# 5-Band_50W_PA_50W_PA.net
KiCad netlist of a schematic drawn in EAGLE
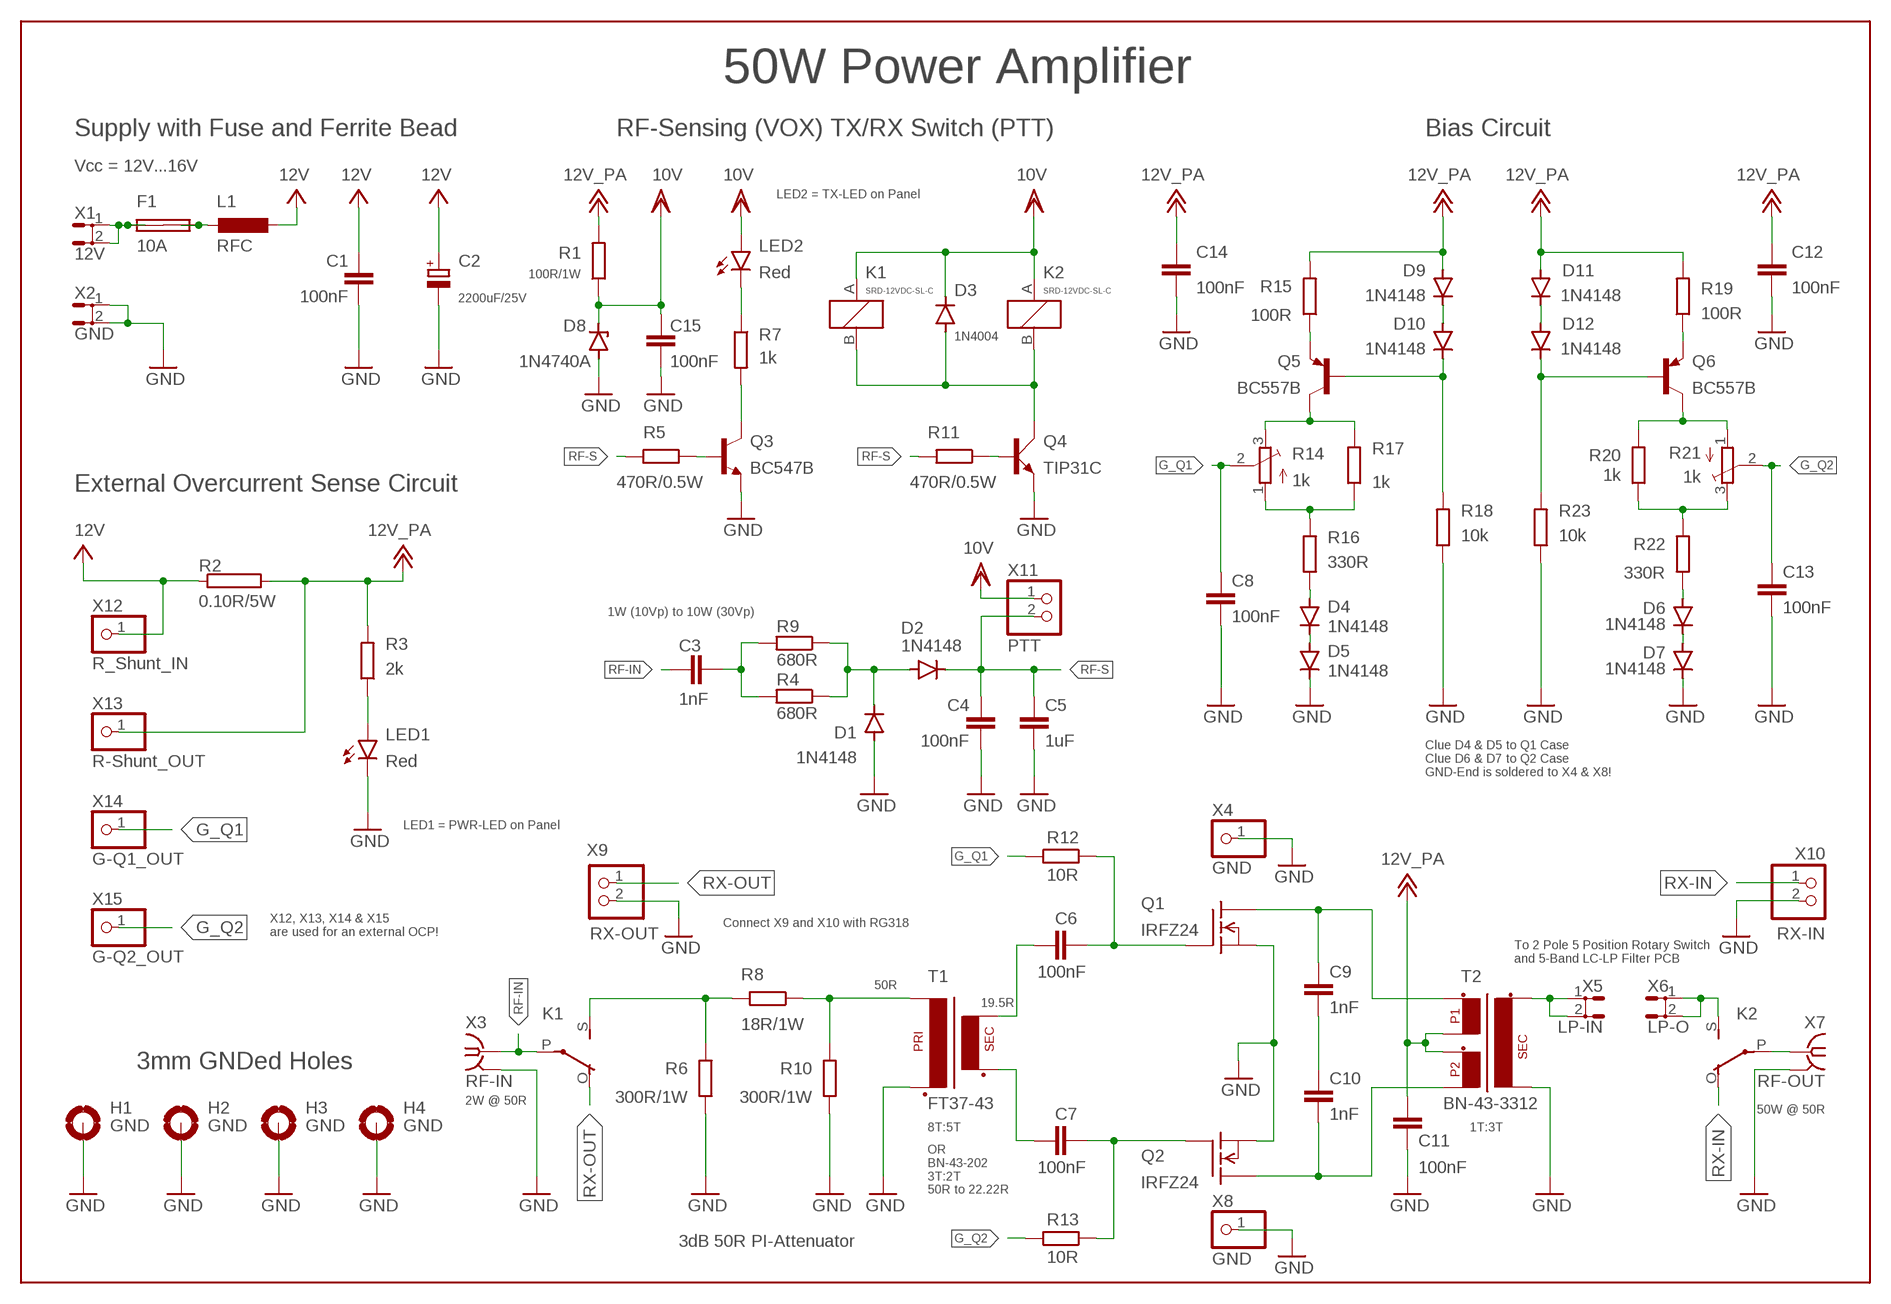
[diagram p0: schematic, sheet 1]

(export (version "E")
  (design (tool "Eeschema 10.0.6"))
  (components
    (comp (ref "C1")
      (value "100nF")
      (footprint "eagle-import:C0805")
      (libsource (lib "eagle-import") (part "C-EUC0805"))
    )
    (comp (ref "C2")
      (value "2200uF/25V")
      (footprint "eagle-import:E7,5-16")
      (libsource (lib "eagle-import") (part "CPOL-EUE7.5-16"))
    )
    (comp (ref "C3")
      (value "1nF")
      (footprint "eagle-import:C0805")
      (libsource (lib "eagle-import") (part "C-EUC0805"))
    )
    (comp (ref "C4")
      (value "100nF")
      (footprint "eagle-import:C0805")
      (libsource (lib "eagle-import") (part "C-EUC0805"))
    )
    (comp (ref "C5")
      (value "1uF")
      (footprint "eagle-import:C0805")
      (libsource (lib "eagle-import") (part "C-EUC0805"))
    )
    (comp (ref "C6")
      (value "100nF")
      (footprint "eagle-import:C0805")
      (libsource (lib "eagle-import") (part "C-EUC0805"))
    )
    (comp (ref "C7")
      (value "100nF")
      (footprint "eagle-import:C0805")
      (libsource (lib "eagle-import") (part "C-EUC0805"))
    )
    (comp (ref "C8")
      (value "100nF")
      (footprint "eagle-import:C0805")
      (libsource (lib "eagle-import") (part "C-EUC0805"))
    )
    (comp (ref "C9")
      (value "1nF")
      (footprint "eagle-import:C1206K")
      (libsource (lib "eagle-import") (part "C-EUC1206K"))
    )
    (comp (ref "C10")
      (value "1nF")
      (footprint "eagle-import:C1206K")
      (libsource (lib "eagle-import") (part "C-EUC1206K"))
    )
    (comp (ref "C11")
      (value "100nF")
      (footprint "eagle-import:C0805")
      (libsource (lib "eagle-import") (part "C-EUC0805"))
    )
    (comp (ref "C12")
      (value "100nF")
      (footprint "eagle-import:C0805")
      (libsource (lib "eagle-import") (part "C-EUC0805"))
    )
    (comp (ref "C13")
      (value "100nF")
      (footprint "eagle-import:C0805")
      (libsource (lib "eagle-import") (part "C-EUC0805"))
    )
    (comp (ref "C14")
      (value "100nF")
      (footprint "eagle-import:C0805")
      (libsource (lib "eagle-import") (part "C-EUC0805"))
    )
    (comp (ref "C15")
      (value "100nF")
      (footprint "eagle-import:C0805")
      (libsource (lib "eagle-import") (part "C-EUC0805"))
    )
    (comp (ref "D1")
      (value "1N4148")
      (footprint "eagle-import:SOD323-W")
      (libsource (lib "eagle-import") (part "DIODE-SOD323-W"))
    )
    (comp (ref "D2")
      (value "1N4148")
      (footprint "eagle-import:SOD323-W")
      (libsource (lib "eagle-import") (part "DIODE-SOD323-W"))
    )
    (comp (ref "D3")
      (value "1N4004")
      (footprint "eagle-import:DO41-10")
      (libsource (lib "eagle-import") (part "1N4004"))
    )
    (comp (ref "D4")
      (value "1N4148")
      (footprint "eagle-import:DO35-7")
      (libsource (lib "eagle-import") (part "1N4148DO35-7"))
    )
    (comp (ref "D5")
      (value "1N4148")
      (footprint "eagle-import:DO35-7")
      (libsource (lib "eagle-import") (part "1N4148DO35-7"))
    )
    (comp (ref "D6")
      (value "1N4148")
      (footprint "eagle-import:DO35-7")
      (libsource (lib "eagle-import") (part "1N4148DO35-7"))
    )
    (comp (ref "D7")
      (value "1N4148")
      (footprint "eagle-import:DO35-7")
      (libsource (lib "eagle-import") (part "1N4148DO35-7"))
    )
    (comp (ref "D8")
      (value "1N4740A")
      (footprint "eagle-import:DO41Z10")
      (libsource (lib "eagle-import") (part "1N4728"))
    )
    (comp (ref "D9")
      (value "1N4148")
      (footprint "eagle-import:SOD323-W")
      (libsource (lib "eagle-import") (part "DIODE-SOD323-W"))
    )
    (comp (ref "D10")
      (value "1N4148")
      (footprint "eagle-import:SOD323-W")
      (libsource (lib "eagle-import") (part "DIODE-SOD323-W"))
    )
    (comp (ref "D11")
      (value "1N4148")
      (footprint "eagle-import:SOD323-W")
      (libsource (lib "eagle-import") (part "DIODE-SOD323-W"))
    )
    (comp (ref "D12")
      (value "1N4148")
      (footprint "eagle-import:SOD323-W")
      (libsource (lib "eagle-import") (part "DIODE-SOD323-W"))
    )
    (comp (ref "F1")
      (value "10A")
      (footprint "eagle-import:SHK20L")
      (libsource (lib "eagle-import") (part "SHK20L"))
    )
    (comp (ref "H1")
      (value "GND")
      (footprint "eagle-import:3,0-PAD")
      (libsource (lib "eagle-import") (part "MOUNT-PAD-ROUND3.0"))
    )
    (comp (ref "H2")
      (value "GND")
      (footprint "eagle-import:3,0-PAD")
      (libsource (lib "eagle-import") (part "MOUNT-PAD-ROUND3.0"))
    )
    (comp (ref "H3")
      (value "GND")
      (footprint "eagle-import:3,0-PAD")
      (libsource (lib "eagle-import") (part "MOUNT-PAD-ROUND3.0"))
    )
    (comp (ref "H4")
      (value "GND")
      (footprint "eagle-import:3,0-PAD")
      (libsource (lib "eagle-import") (part "MOUNT-PAD-ROUND3.0"))
    )
    (comp (ref "K1")
      (value "SRD-12VDC-SL-C")
      (footprint "eagle-import:SRD-12VDC-SL-C")
      (libsource (lib "eagle-import") (part "SRD-12VDC-SL-C"))
    )
    (comp (ref "K2")
      (value "SRD-12VDC-SL-C")
      (footprint "eagle-import:SRD-12VDC-SL-C")
      (libsource (lib "eagle-import") (part "SRD-12VDC-SL-C"))
    )
    (comp (ref "L1")
      (value "RFC")
      (footprint "eagle-import:T50-6SMD")
      (libsource (lib "eagle-import") (part "T50-6"))
    )
    (comp (ref "LED1")
      (value "Red")
      (footprint "eagle-import:LED5MM")
      (libsource (lib "eagle-import") (part "LED5MM"))
    )
    (comp (ref "LED2")
      (value "Red")
      (footprint "eagle-import:LED5MM")
      (libsource (lib "eagle-import") (part "LED5MM"))
    )
    (comp (ref "Q1")
      (value "IRFZ24")
      (footprint "eagle-import:TO220")
      (libsource (lib "eagle-import") (part "IRF510"))
    )
    (comp (ref "Q2")
      (value "IRFZ24")
      (footprint "eagle-import:TO220")
      (libsource (lib "eagle-import") (part "IRF510"))
    )
    (comp (ref "Q3")
      (value "BC547B")
      (footprint "eagle-import:TO92-CBE")
      (libsource (lib "eagle-import") (part "-NPN-TO92-CBEBC547B"))
    )
    (comp (ref "Q4")
      (value "TIP31C")
      (footprint "eagle-import:TO220AV")
      (libsource (lib "eagle-import") (part "TIP41C"))
    )
    (comp (ref "Q5")
      (value "BC557B")
      (footprint "eagle-import:TO92-EBC")
      (libsource (lib "eagle-import") (part "BC557B"))
    )
    (comp (ref "Q6")
      (value "BC557B")
      (footprint "eagle-import:TO92-EBC")
      (libsource (lib "eagle-import") (part "BC557B"))
    )
    (comp (ref "R1")
      (value "100R/1W")
      (footprint "eagle-import:0414_15")
      (libsource (lib "eagle-import") (part "R-EU_0414/15"))
    )
    (comp (ref "R2")
      (value "0.10R/5W")
      (footprint "eagle-import:MNS-5")
      (libsource (lib "eagle-import") (part "RMNS-5"))
    )
    (comp (ref "R3")
      (value "2k")
      (footprint "eagle-import:R0805")
      (libsource (lib "eagle-import") (part "R-EU_R0805"))
    )
    (comp (ref "R4")
      (value "680R")
      (footprint "eagle-import:R0805")
      (libsource (lib "eagle-import") (part "R-EU_R0805"))
    )
    (comp (ref "R5")
      (value "470R/0.5W")
      (footprint "eagle-import:0207_10")
      (libsource (lib "eagle-import") (part "R-EU_0207/10"))
    )
    (comp (ref "R6")
      (value "300R/1W")
      (footprint "eagle-import:0414_15")
      (libsource (lib "eagle-import") (part "R-EU_0414/15"))
    )
    (comp (ref "R7")
      (value "1k")
      (footprint "eagle-import:R0805")
      (libsource (lib "eagle-import") (part "R-EU_R0805"))
    )
    (comp (ref "R8")
      (value "18R/1W")
      (footprint "eagle-import:0414_15")
      (libsource (lib "eagle-import") (part "R-EU_0414/15"))
    )
    (comp (ref "R9")
      (value "680R")
      (footprint "eagle-import:R0805")
      (libsource (lib "eagle-import") (part "R-EU_R0805"))
    )
    (comp (ref "R10")
      (value "300R/1W")
      (footprint "eagle-import:0414_15")
      (libsource (lib "eagle-import") (part "R-EU_0414/15"))
    )
    (comp (ref "R11")
      (value "470R/0.5W")
      (footprint "eagle-import:0207_10")
      (libsource (lib "eagle-import") (part "R-EU_0207/10"))
    )
    (comp (ref "R12")
      (value "10R")
      (footprint "eagle-import:0207_10")
      (libsource (lib "eagle-import") (part "R-EU_0207/10"))
    )
    (comp (ref "R13")
      (value "10R")
      (footprint "eagle-import:0207_10")
      (libsource (lib "eagle-import") (part "R-EU_0207/10"))
    )
    (comp (ref "R14")
      (value "1k")
      (footprint "eagle-import:3223G")
      (libsource (lib "eagle-import") (part "TRIM_EU-3223G"))
    )
    (comp (ref "R15")
      (value "100R")
      (footprint "eagle-import:R0805")
      (libsource (lib "eagle-import") (part "R-EU_R0805"))
    )
    (comp (ref "R16")
      (value "330R")
      (footprint "eagle-import:R0805")
      (libsource (lib "eagle-import") (part "R-EU_R0805"))
    )
    (comp (ref "R17")
      (value "1k")
      (footprint "eagle-import:R0805")
      (libsource (lib "eagle-import") (part "R-EU_R0805"))
    )
    (comp (ref "R18")
      (value "10k")
      (footprint "eagle-import:R0805")
      (libsource (lib "eagle-import") (part "R-EU_R0805"))
    )
    (comp (ref "R19")
      (value "100R")
      (footprint "eagle-import:R0805")
      (libsource (lib "eagle-import") (part "R-EU_R0805"))
    )
    (comp (ref "R20")
      (value "1k")
      (footprint "eagle-import:R0805")
      (libsource (lib "eagle-import") (part "R-EU_R0805"))
    )
    (comp (ref "R21")
      (value "1k")
      (footprint "eagle-import:3223G")
      (libsource (lib "eagle-import") (part "TRIM_EU-3223G"))
    )
    (comp (ref "R22")
      (value "330R")
      (footprint "eagle-import:R0805")
      (libsource (lib "eagle-import") (part "R-EU_R0805"))
    )
    (comp (ref "R23")
      (value "10k")
      (footprint "eagle-import:R0805")
      (libsource (lib "eagle-import") (part "R-EU_R0805"))
    )
    (comp (ref "T1")
      (value "FT37-43")
      (footprint "eagle-import:FT37-43SMD")
      (libsource (lib "eagle-import") (part "FT37-43"))
    )
    (comp (ref "T2")
      (value "BN-43-3312")
      (footprint "eagle-import:BN-43-3312CENTERTAPSMD")
      (libsource (lib "eagle-import") (part "BN-43-3312CENTERTAP"))
    )
    (comp (ref "X1")
      (value "12V")
      (footprint "eagle-import:ST6,3")
      (libsource (lib "eagle-import") (part "ST6,3"))
    )
    (comp (ref "X2")
      (value "GND")
      (footprint "eagle-import:ST6,3")
      (libsource (lib "eagle-import") (part "ST6,3"))
    )
    (comp (ref "X3")
      (value "RF-IN")
      (footprint "eagle-import:J502-ND-142-0711-821_826")
      (fields (field (name "MF") "JOHNSON COMPONENTS") (field (name "MPN") "142-0711-821"))
      (libsource (lib "eagle-import") (part "SMA-PCB-CON142-0711-821/826"))
    )
    (comp (ref "X4")
      (value "GND")
      (footprint "eagle-import:1X01")
      (libsource (lib "eagle-import") (part "PINHD-1X1"))
    )
    (comp (ref "X5")
      (value "LP-IN")
      (footprint "eagle-import:ST6,3")
      (libsource (lib "eagle-import") (part "ST6,3"))
    )
    (comp (ref "X6")
      (value "LP-O")
      (footprint "eagle-import:ST6,3")
      (libsource (lib "eagle-import") (part "ST6,3"))
    )
    (comp (ref "X7")
      (value "RF-OUT")
      (footprint "eagle-import:J502-ND-142-0711-821_826")
      (fields (field (name "MF") "JOHNSON COMPONENTS") (field (name "MPN") "142-0711-821"))
      (libsource (lib "eagle-import") (part "SMA-PCB-CON142-0711-821/826"))
    )
    (comp (ref "X8")
      (value "GND")
      (footprint "eagle-import:1X01")
      (libsource (lib "eagle-import") (part "PINHD-1X1"))
    )
    (comp (ref "X9")
      (value "RX-OUT")
      (footprint "eagle-import:1X02")
      (libsource (lib "eagle-import") (part "PINHD-1X2"))
    )
    (comp (ref "X10")
      (value "RX-IN")
      (footprint "eagle-import:1X02")
      (libsource (lib "eagle-import") (part "PINHD-1X2"))
    )
    (comp (ref "X11")
      (value "PTT")
      (footprint "eagle-import:1X02")
      (libsource (lib "eagle-import") (part "PINHD-1X2"))
    )
    (comp (ref "X12")
      (value "R_Shunt_IN")
      (footprint "eagle-import:1X01")
      (libsource (lib "eagle-import") (part "PINHD-1X1"))
    )
    (comp (ref "X13")
      (value "R-Shunt_OUT")
      (footprint "eagle-import:1X01")
      (libsource (lib "eagle-import") (part "PINHD-1X1"))
    )
    (comp (ref "X14")
      (value "G-Q1_OUT")
      (footprint "eagle-import:1X01")
      (libsource (lib "eagle-import") (part "PINHD-1X1"))
    )
    (comp (ref "X15")
      (value "G-Q2_OUT")
      (footprint "eagle-import:1X01")
      (libsource (lib "eagle-import") (part "PINHD-1X1"))
    )
  )
  (nets
    (net (code "1") (name "10V") (class "Default")
      (node (ref "C15") (pin "2") (pinfunction "2_2") (pintype "passive"))
      (node (ref "D3") (pin "C") (pinfunction "C_C") (pintype "passive"))
      (node (ref "D8") (pin "C") (pinfunction "C_C") (pintype "passive"))
      (node (ref "K1") (pin "A") (pinfunction "A_A") (pintype "passive"))
      (node (ref "K2") (pin "A") (pinfunction "A_A") (pintype "passive"))
      (node (ref "LED2") (pin "A") (pinfunction "A_A") (pintype "passive"))
      (node (ref "R1") (pin "1") (pinfunction "1_1") (pintype "passive"))
      (node (ref "X11") (pin "1") (pinfunction "1_1") (pintype "passive"))
    )
    (net (code "2") (name "12V") (class "Default")
      (node (ref "C1") (pin "2") (pinfunction "2_2") (pintype "passive"))
      (node (ref "C2") (pin "+") (pinfunction "+_+") (pintype "passive"))
      (node (ref "L1") (pin "P$2") (pinfunction "2_P$2") (pintype "passive"))
      (node (ref "R2") (pin "1") (pinfunction "1_1") (pintype "passive"))
      (node (ref "X12") (pin "1") (pinfunction "1_1") (pintype "passive"))
    )
    (net (code "3") (name "12V_PA") (class "Default")
      (node (ref "C11") (pin "2") (pinfunction "2_2") (pintype "passive"))
      (node (ref "C12") (pin "2") (pinfunction "2_2") (pintype "passive"))
      (node (ref "C14") (pin "2") (pinfunction "2_2") (pintype "passive"))
      (node (ref "D11") (pin "A") (pinfunction "A_A") (pintype "passive"))
      (node (ref "D9") (pin "A") (pinfunction "A_A") (pintype "passive"))
      (node (ref "R1") (pin "2") (pinfunction "2_2") (pintype "passive"))
      (node (ref "R15") (pin "2") (pinfunction "2_2") (pintype "passive"))
      (node (ref "R19") (pin "2") (pinfunction "2_2") (pintype "passive"))
      (node (ref "R2") (pin "2") (pinfunction "2_2") (pintype "passive"))
      (node (ref "R3") (pin "2") (pinfunction "2_2") (pintype "passive"))
      (node (ref "T2") (pin "P$2") (pinfunction "P1_2_P$2") (pintype "passive"))
      (node (ref "T2") (pin "P$3") (pinfunction "P2_1_P$3") (pintype "passive"))
      (node (ref "X13") (pin "1") (pinfunction "1_1") (pintype "passive"))
    )
    (net (code "4") (name "GND") (class "Default")
      (node (ref "C1") (pin "1") (pinfunction "1_1") (pintype "passive"))
      (node (ref "C11") (pin "1") (pinfunction "1_1") (pintype "passive"))
      (node (ref "C12") (pin "1") (pinfunction "1_1") (pintype "passive"))
      (node (ref "C13") (pin "1") (pinfunction "1_1") (pintype "passive"))
      (node (ref "C14") (pin "1") (pinfunction "1_1") (pintype "passive"))
      (node (ref "C15") (pin "1") (pinfunction "1_1") (pintype "passive"))
      (node (ref "C2") (pin "-") (pinfunction "-_-") (pintype "passive"))
      (node (ref "C4") (pin "1") (pinfunction "1_1") (pintype "passive"))
      (node (ref "C5") (pin "1") (pinfunction "1_1") (pintype "passive"))
      (node (ref "C8") (pin "1") (pinfunction "1_1") (pintype "passive"))
      (node (ref "D1") (pin "A") (pinfunction "A_A") (pintype "passive"))
      (node (ref "D5") (pin "C") (pinfunction "C_C") (pintype "passive"))
      (node (ref "D7") (pin "C") (pinfunction "C_C") (pintype "passive"))
      (node (ref "D8") (pin "A") (pinfunction "A_A") (pintype "passive"))
      (node (ref "H1") (pin "B3,0") (pinfunction "MOUNT_B3,0") (pintype "passive"))
      (node (ref "H2") (pin "B3,0") (pinfunction "MOUNT_B3,0") (pintype "passive"))
      (node (ref "H3") (pin "B3,0") (pinfunction "MOUNT_B3,0") (pintype "passive"))
      (node (ref "H4") (pin "B3,0") (pinfunction "MOUNT_B3,0") (pintype "passive"))
      (node (ref "LED1") (pin "K") (pinfunction "C_K") (pintype "passive"))
      (node (ref "Q1") (pin "3") (pinfunction "S_3") (pintype "passive"))
      (node (ref "Q2") (pin "3") (pinfunction "S_3") (pintype "passive"))
      (node (ref "Q3") (pin "E") (pinfunction "E_E") (pintype "passive"))
      (node (ref "Q4") (pin "E") (pinfunction "E_E") (pintype "passive"))
      (node (ref "R10") (pin "1") (pinfunction "1_1") (pintype "passive"))
      (node (ref "R18") (pin "1") (pinfunction "1_1") (pintype "passive"))
      (node (ref "R23") (pin "1") (pinfunction "1_1") (pintype "passive"))
      (node (ref "R6") (pin "1") (pinfunction "1_1") (pintype "passive"))
      (node (ref "T1") (pin "P$2") (pinfunction "P2_P$2") (pintype "passive"))
      (node (ref "T2") (pin "S$2") (pinfunction "S2_S$2") (pintype "passive"))
      (node (ref "X10") (pin "2") (pinfunction "2_2") (pintype "passive"))
      (node (ref "X2") (pin "1") (pinfunction "1_1") (pintype "passive"))
      (node (ref "X2") (pin "2") (pinfunction "2_2") (pintype "passive"))
      (node (ref "X3") (pin "G@1") (pinfunction "GND_G@1") (pintype "passive"))
      (node (ref "X3") (pin "G@2") (pinfunction "GND_G@2") (pintype "passive"))
      (node (ref "X3") (pin "G@3") (pinfunction "GND_G@3") (pintype "passive"))
      (node (ref "X3") (pin "G@4") (pinfunction "GND_G@4") (pintype "passive"))
      (node (ref "X4") (pin "1") (pinfunction "1_1") (pintype "passive"))
      (node (ref "X7") (pin "G@1") (pinfunction "GND_G@1") (pintype "passive"))
      (node (ref "X7") (pin "G@2") (pinfunction "GND_G@2") (pintype "passive"))
      (node (ref "X7") (pin "G@3") (pinfunction "GND_G@3") (pintype "passive"))
      (node (ref "X7") (pin "G@4") (pinfunction "GND_G@4") (pintype "passive"))
      (node (ref "X8") (pin "1") (pinfunction "1_1") (pintype "passive"))
      (node (ref "X9") (pin "2") (pinfunction "2_2") (pintype "passive"))
    )
    (net (code "5") (name "G_Q1") (class "Default")
      (node (ref "C8") (pin "2") (pinfunction "2_2") (pintype "passive"))
      (node (ref "R12") (pin "2") (pinfunction "2_2") (pintype "passive"))
      (node (ref "R14") (pin "2") (pinfunction "S_2") (pintype "passive"))
      (node (ref "X14") (pin "1") (pinfunction "1_1") (pintype "passive"))
    )
    (net (code "6") (name "G_Q2") (class "Default")
      (node (ref "C13") (pin "2") (pinfunction "2_2") (pintype "passive"))
      (node (ref "R13") (pin "2") (pinfunction "2_2") (pintype "passive"))
      (node (ref "R21") (pin "2") (pinfunction "S_2") (pintype "passive"))
      (node (ref "X15") (pin "1") (pinfunction "1_1") (pintype "passive"))
    )
    (net (code "7") (name "Net-(C3-Pad1)") (class "Default")
      (node (ref "C3") (pin "1") (pinfunction "1_1") (pintype "passive"))
      (node (ref "R4") (pin "2") (pinfunction "2_2") (pintype "passive"))
      (node (ref "R9") (pin "2") (pinfunction "2_2") (pintype "passive"))
    )
    (net (code "8") (name "Net-(C10-Pad1)") (class "Default")
      (node (ref "C10") (pin "1") (pinfunction "1_1") (pintype "passive"))
      (node (ref "C9") (pin "2") (pinfunction "2_2") (pintype "passive"))
    )
    (net (code "9") (name "Net-(D1-PadC)") (class "Default")
      (node (ref "D1") (pin "C") (pinfunction "C_C") (pintype "passive"))
      (node (ref "D2") (pin "A") (pinfunction "A_A") (pintype "passive"))
      (node (ref "R4") (pin "1") (pinfunction "1_1") (pintype "passive"))
      (node (ref "R9") (pin "1") (pinfunction "1_1") (pintype "passive"))
    )
    (net (code "10") (name "Net-(D3-PadA)") (class "Default")
      (node (ref "D3") (pin "A") (pinfunction "A_A") (pintype "passive"))
      (node (ref "K1") (pin "B") (pinfunction "B_B") (pintype "passive"))
      (node (ref "K2") (pin "B") (pinfunction "B_B") (pintype "passive"))
      (node (ref "Q4") (pin "C") (pinfunction "C_C") (pintype "passive"))
    )
    (net (code "11") (name "Net-(D4-PadA)") (class "Default")
      (node (ref "D4") (pin "A") (pinfunction "A_A") (pintype "passive"))
      (node (ref "R16") (pin "1") (pinfunction "1_1") (pintype "passive"))
    )
    (net (code "12") (name "Net-(D4-PadC)") (class "Default")
      (node (ref "D4") (pin "C") (pinfunction "C_C") (pintype "passive"))
      (node (ref "D5") (pin "A") (pinfunction "A_A") (pintype "passive"))
    )
    (net (code "13") (name "Net-(D6-PadA)") (class "Default")
      (node (ref "D6") (pin "A") (pinfunction "A_A") (pintype "passive"))
      (node (ref "R22") (pin "1") (pinfunction "1_1") (pintype "passive"))
    )
    (net (code "14") (name "Net-(D6-PadC)") (class "Default")
      (node (ref "D6") (pin "C") (pinfunction "C_C") (pintype "passive"))
      (node (ref "D7") (pin "A") (pinfunction "A_A") (pintype "passive"))
    )
    (net (code "15") (name "Net-(D10-PadA)") (class "Default")
      (node (ref "D10") (pin "A") (pinfunction "A_A") (pintype "passive"))
      (node (ref "D9") (pin "C") (pinfunction "C_C") (pintype "passive"))
    )
    (net (code "16") (name "Net-(D10-PadC)") (class "Default")
      (node (ref "D10") (pin "C") (pinfunction "C_C") (pintype "passive"))
      (node (ref "Q5") (pin "B") (pinfunction "B_B") (pintype "passive"))
      (node (ref "R18") (pin "2") (pinfunction "2_2") (pintype "passive"))
    )
    (net (code "17") (name "Net-(D11-PadC)") (class "Default")
      (node (ref "D11") (pin "C") (pinfunction "C_C") (pintype "passive"))
      (node (ref "D12") (pin "A") (pinfunction "A_A") (pintype "passive"))
    )
    (net (code "18") (name "Net-(D12-PadC)") (class "Default")
      (node (ref "D12") (pin "C") (pinfunction "C_C") (pintype "passive"))
      (node (ref "Q6") (pin "B") (pinfunction "B_B") (pintype "passive"))
      (node (ref "R23") (pin "2") (pinfunction "2_2") (pintype "passive"))
    )
    (net (code "19") (name "Net-(F1-Pad1A)") (class "Default")
      (node (ref "F1") (pin "1A") (pinfunction "1A_1A") (pintype "passive"))
      (node (ref "F1") (pin "1B") (pinfunction "1B_1B") (pintype "passive"))
      (node (ref "X1") (pin "1") (pinfunction "1_1") (pintype "passive"))
      (node (ref "X1") (pin "2") (pinfunction "2_2") (pintype "passive"))
    )
    (net (code "20") (name "Net-(K1-PadS)") (class "Default")
      (node (ref "K1") (pin "S") (pinfunction "S_S") (pintype "passive"))
      (node (ref "R6") (pin "2") (pinfunction "2_2") (pintype "passive"))
      (node (ref "R8") (pin "2") (pinfunction "2_2") (pintype "passive"))
    )
    (net (code "21") (name "Net-(K2-PadS)") (class "Default")
      (node (ref "K2") (pin "S") (pinfunction "S_S") (pintype "passive"))
      (node (ref "X6") (pin "1") (pinfunction "1_1") (pintype "passive"))
      (node (ref "X6") (pin "2") (pinfunction "2_2") (pintype "passive"))
    )
    (net (code "22") (name "Net-(L1-1)") (class "Default")
      (node (ref "F1") (pin "2A") (pinfunction "2A_2A") (pintype "passive"))
      (node (ref "F1") (pin "2B") (pinfunction "2B_2B") (pintype "passive"))
      (node (ref "L1") (pin "P$1") (pinfunction "1_P$1") (pintype "passive"))
    )
    (net (code "23") (name "Net-(LED1-PadA)") (class "Default")
      (node (ref "LED1") (pin "A") (pinfunction "A_A") (pintype "passive"))
      (node (ref "R3") (pin "1") (pinfunction "1_1") (pintype "passive"))
    )
    (net (code "24") (name "Net-(LED2-C)") (class "Default")
      (node (ref "LED2") (pin "K") (pinfunction "C_K") (pintype "passive"))
      (node (ref "R7") (pin "1") (pinfunction "1_1") (pintype "passive"))
    )
    (net (code "25") (name "Net-(Q1-D)") (class "Default")
      (node (ref "C9") (pin "1") (pinfunction "1_1") (pintype "passive"))
      (node (ref "Q1") (pin "2") (pinfunction "D_2") (pintype "passive"))
      (node (ref "T2") (pin "P$1") (pinfunction "P1_1_P$1") (pintype "passive"))
    )
    (net (code "26") (name "Net-(Q1-G)") (class "Default")
      (node (ref "C6") (pin "1") (pinfunction "1_1") (pintype "passive"))
      (node (ref "Q1") (pin "1") (pinfunction "G_1") (pintype "passive"))
      (node (ref "R12") (pin "1") (pinfunction "1_1") (pintype "passive"))
    )
    (net (code "27") (name "Net-(Q2-D)") (class "Default")
      (node (ref "C10") (pin "2") (pinfunction "2_2") (pintype "passive"))
      (node (ref "Q2") (pin "2") (pinfunction "D_2") (pintype "passive"))
      (node (ref "T2") (pin "P$4") (pinfunction "P2_2_P$4") (pintype "passive"))
    )
    (net (code "28") (name "Net-(Q2-G)") (class "Default")
      (node (ref "C7") (pin "1") (pinfunction "1_1") (pintype "passive"))
      (node (ref "Q2") (pin "1") (pinfunction "G_1") (pintype "passive"))
      (node (ref "R13") (pin "1") (pinfunction "1_1") (pintype "passive"))
    )
    (net (code "29") (name "Net-(Q3-PadB)") (class "Default")
      (node (ref "Q3") (pin "B") (pinfunction "B_B") (pintype "passive"))
      (node (ref "R5") (pin "1") (pinfunction "1_1") (pintype "passive"))
    )
    (net (code "30") (name "Net-(Q3-PadC)") (class "Default")
      (node (ref "Q3") (pin "C") (pinfunction "C_C") (pintype "passive"))
      (node (ref "R7") (pin "2") (pinfunction "2_2") (pintype "passive"))
    )
    (net (code "31") (name "Net-(Q4-PadB)") (class "Default")
      (node (ref "Q4") (pin "B") (pinfunction "B_B") (pintype "passive"))
      (node (ref "R11") (pin "1") (pinfunction "1_1") (pintype "passive"))
    )
    (net (code "32") (name "Net-(Q5-PadE)") (class "Default")
      (node (ref "Q5") (pin "E") (pinfunction "E_E") (pintype "passive"))
      (node (ref "R15") (pin "1") (pinfunction "1_1") (pintype "passive"))
    )
    (net (code "33") (name "Net-(Q6-PadE)") (class "Default")
      (node (ref "Q6") (pin "E") (pinfunction "E_E") (pintype "passive"))
      (node (ref "R19") (pin "1") (pinfunction "1_1") (pintype "passive"))
    )
    (net (code "34") (name "Net-(R14-A)") (class "Default")
      (node (ref "R14") (pin "1") (pinfunction "A_1") (pintype "passive"))
      (node (ref "R16") (pin "2") (pinfunction "2_2") (pintype "passive"))
      (node (ref "R17") (pin "1") (pinfunction "1_1") (pintype "passive"))
    )
    (net (code "35") (name "Net-(R14-E)") (class "Default")
      (node (ref "Q5") (pin "C") (pinfunction "C_C") (pintype "passive"))
      (node (ref "R14") (pin "3") (pinfunction "E_3") (pintype "passive"))
      (node (ref "R17") (pin "2") (pinfunction "2_2") (pintype "passive"))
    )
    (net (code "36") (name "Net-(R21-A)") (class "Default")
      (node (ref "Q6") (pin "C") (pinfunction "C_C") (pintype "passive"))
      (node (ref "R20") (pin "2") (pinfunction "2_2") (pintype "passive"))
      (node (ref "R21") (pin "1") (pinfunction "A_1") (pintype "passive"))
    )
    (net (code "37") (name "Net-(R21-E)") (class "Default")
      (node (ref "R20") (pin "1") (pinfunction "1_1") (pintype "passive"))
      (node (ref "R21") (pin "3") (pinfunction "E_3") (pintype "passive"))
      (node (ref "R22") (pin "2") (pinfunction "2_2") (pintype "passive"))
    )
    (net (code "38") (name "Net-(T1-P1)") (class "Default")
      (node (ref "R10") (pin "2") (pinfunction "2_2") (pintype "passive"))
      (node (ref "R8") (pin "1") (pinfunction "1_1") (pintype "passive"))
      (node (ref "T1") (pin "P$1") (pinfunction "P1_P$1") (pintype "passive"))
    )
    (net (code "39") (name "Net-(T1-S1)") (class "Default")
      (node (ref "C6") (pin "2") (pinfunction "2_2") (pintype "passive"))
      (node (ref "T1") (pin "S$1") (pinfunction "S1_S$1") (pintype "passive"))
    )
    (net (code "40") (name "Net-(T1-S2)") (class "Default")
      (node (ref "C7") (pin "2") (pinfunction "2_2") (pintype "passive"))
      (node (ref "T1") (pin "S$2") (pinfunction "S2_S$2") (pintype "passive"))
    )
    (net (code "41") (name "Net-(T2-S1)") (class "Default")
      (node (ref "T2") (pin "S$1") (pinfunction "S1_S$1") (pintype "passive"))
      (node (ref "X5") (pin "1") (pinfunction "1_1") (pintype "passive"))
      (node (ref "X5") (pin "2") (pinfunction "2_2") (pintype "passive"))
    )
    (net (code "42") (name "Net-(X7-RF)") (class "Default")
      (node (ref "K2") (pin "P") (pinfunction "P_P") (pintype "passive"))
      (node (ref "X7") (pin "1") (pinfunction "RF_1") (pintype "passive"))
    )
    (net (code "43") (name "RF-IN") (class "Default")
      (node (ref "C3") (pin "2") (pinfunction "2_2") (pintype "passive"))
      (node (ref "K1") (pin "P") (pinfunction "P_P") (pintype "passive"))
      (node (ref "X3") (pin "1") (pinfunction "RF_1") (pintype "passive"))
    )
    (net (code "44") (name "RF-S") (class "Default")
      (node (ref "C4") (pin "2") (pinfunction "2_2") (pintype "passive"))
      (node (ref "C5") (pin "2") (pinfunction "2_2") (pintype "passive"))
      (node (ref "D2") (pin "C") (pinfunction "C_C") (pintype "passive"))
      (node (ref "R11") (pin "2") (pinfunction "2_2") (pintype "passive"))
      (node (ref "R5") (pin "2") (pinfunction "2_2") (pintype "passive"))
      (node (ref "X11") (pin "2") (pinfunction "2_2") (pintype "passive"))
    )
    (net (code "45") (name "RX-IN") (class "Default")
      (node (ref "K2") (pin "O") (pinfunction "O_O") (pintype "passive"))
      (node (ref "X10") (pin "1") (pinfunction "1_1") (pintype "passive"))
    )
    (net (code "46") (name "RX-OUT") (class "Default")
      (node (ref "K1") (pin "O") (pinfunction "O_O") (pintype "passive"))
      (node (ref "X9") (pin "1") (pinfunction "1_1") (pintype "passive"))
    )
  )
)
